# part_2.net
KiCad netlist of a schematic drawn in EAGLE
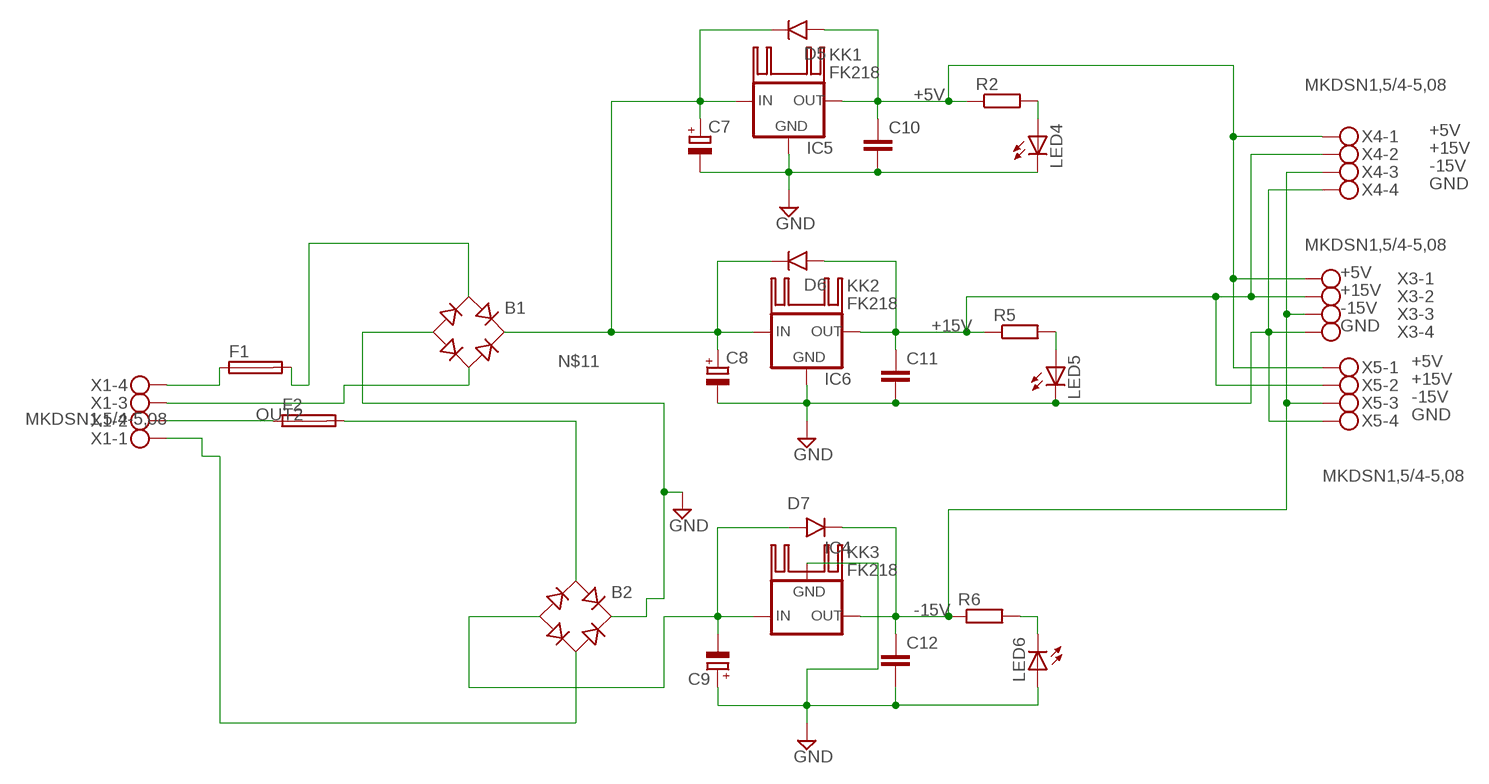
[diagram p0: schematic, sheet 1]

(export (version "E")
  (design (tool "Eeschema 10.0.6"))
  (components
    (comp (ref "B1")
      (value "RB1A")
      (footprint "eagle-import:RB1A")
      (libsource (lib "eagle-import") (part "RB1A"))
    )
    (comp (ref "B2")
      (value "RB1A")
      (footprint "eagle-import:RB1A")
      (libsource (lib "eagle-import") (part "RB1A"))
    )
    (comp (ref "C7")
      (value "CPOL-EUE7.5-18")
      (footprint "eagle-import:E7,5-18")
      (libsource (lib "eagle-import") (part "CPOL-EUE7.5-18"))
    )
    (comp (ref "C8")
      (value "CPOL-EUE7.5-18")
      (footprint "eagle-import:E7,5-18")
      (libsource (lib "eagle-import") (part "CPOL-EUE7.5-18"))
    )
    (comp (ref "C9")
      (value "CPOL-EUE7.5-18")
      (footprint "eagle-import:E7,5-18")
      (libsource (lib "eagle-import") (part "CPOL-EUE7.5-18"))
    )
    (comp (ref "C10")
      (value "C-EU050-025X075")
      (footprint "eagle-import:C050-025X075")
      (libsource (lib "eagle-import") (part "C-EU050-025X075"))
    )
    (comp (ref "C11")
      (value "C-EU050-025X075")
      (footprint "eagle-import:C050-025X075")
      (libsource (lib "eagle-import") (part "C-EU050-025X075"))
    )
    (comp (ref "C12")
      (value "C-EU050-025X075")
      (footprint "eagle-import:C050-025X075")
      (libsource (lib "eagle-import") (part "C-EU050-025X075"))
    )
    (comp (ref "D5")
      (value "1N4001")
      (footprint "eagle-import:DO41-10")
      (libsource (lib "eagle-import") (part "1N4001"))
    )
    (comp (ref "D6")
      (value "1N4001")
      (footprint "eagle-import:DO41-10")
      (libsource (lib "eagle-import") (part "1N4001"))
    )
    (comp (ref "D7")
      (value "1N4001")
      (footprint "eagle-import:DO41-10")
      (libsource (lib "eagle-import") (part "1N4001"))
    )
    (comp (ref "F1")
      (value "SH22,5A")
      (footprint "eagle-import:SH22,5A")
      (fields (field (name "MPN") "0031.7701.11"))
      (libsource (lib "eagle-import") (part "SH22,5A"))
    )
    (comp (ref "F2")
      (value "SH22,5A")
      (footprint "eagle-import:SH22,5A")
      (fields (field (name "MPN") "0031.7701.11"))
      (libsource (lib "eagle-import") (part "SH22,5A"))
    )
    (comp (ref "IC4")
      (value "79XXS")
      (footprint "eagle-import:79XXS")
      (libsource (lib "eagle-import") (part "79XXS"))
    )
    (comp (ref "IC5")
      (value "78XXS")
      (footprint "eagle-import:78XXS")
      (libsource (lib "eagle-import") (part "78XXS"))
    )
    (comp (ref "IC6")
      (value "78XXS")
      (footprint "eagle-import:78XXS")
      (libsource (lib "eagle-import") (part "78XXS"))
    )
    (comp (ref "KK1")
      (value "FK218")
      (footprint "eagle-import:FK218")
      (libsource (lib "eagle-import") (part "FK218"))
    )
    (comp (ref "KK2")
      (value "FK218")
      (footprint "eagle-import:FK218")
      (libsource (lib "eagle-import") (part "FK218"))
    )
    (comp (ref "KK3")
      (value "FK218")
      (footprint "eagle-import:FK218")
      (libsource (lib "eagle-import") (part "FK218"))
    )
    (comp (ref "LED4")
      (value "LED5MM")
      (footprint "eagle-import:LED5MM")
      (libsource (lib "eagle-import") (part "LED5MM"))
    )
    (comp (ref "LED5")
      (value "LED5MM")
      (footprint "eagle-import:LED5MM")
      (libsource (lib "eagle-import") (part "LED5MM"))
    )
    (comp (ref "LED6")
      (value "LED5MM")
      (footprint "eagle-import:LED5MM")
      (libsource (lib "eagle-import") (part "LED5MM"))
    )
    (comp (ref "R2")
      (value "R-EU_0207/15")
      (footprint "eagle-import:0207_15")
      (libsource (lib "eagle-import") (part "R-EU_0207/15"))
    )
    (comp (ref "R5")
      (value "R-EU_0207/15")
      (footprint "eagle-import:0207_15")
      (libsource (lib "eagle-import") (part "R-EU_0207/15"))
    )
    (comp (ref "R6")
      (value "R-EU_0207/15")
      (footprint "eagle-import:0207_15")
      (libsource (lib "eagle-import") (part "R-EU_0207/15"))
    )
    (comp (ref "X1")
      (value "MKDSN1,5/4-5,08")
      (footprint "eagle-import:MKDSN1,5_4-5,08")
      (libsource (lib "eagle-import") (part "MKDSN1,5/4-5,08"))
    )
    (comp (ref "X3")
      (value "MKDSN1,5/4-5,08")
      (footprint "eagle-import:MKDSN1,5_4-5,08")
      (libsource (lib "eagle-import") (part "MKDSN1,5/4-5,08"))
    )
    (comp (ref "X4")
      (value "MKDSN1,5/4-5,08")
      (footprint "eagle-import:MKDSN1,5_4-5,08")
      (libsource (lib "eagle-import") (part "MKDSN1,5/4-5,08"))
    )
    (comp (ref "X5")
      (value "MKDSN1,5/4-5,08")
      (footprint "eagle-import:MKDSN1,5_4-5,08")
      (libsource (lib "eagle-import") (part "MKDSN1,5/4-5,08"))
    )
  )
  (nets
    (net (code "1") (name "/+5V") (class "Default")
      (node (ref "C10") (pin "1") (pinfunction "1_1") (pintype "passive"))
      (node (ref "D5") (pin "A") (pinfunction "ANODE_A") (pintype "passive"))
      (node (ref "IC5") (pin "OUT") (pinfunction "OUT_OUT") (pintype "passive"))
      (node (ref "R2") (pin "1") (pinfunction "1_1") (pintype "passive"))
      (node (ref "X3") (pin "1") (pinfunction "KL_1") (pintype "passive"))
      (node (ref "X4") (pin "1") (pinfunction "KL_1") (pintype "passive"))
      (node (ref "X5") (pin "1") (pinfunction "KL_1") (pintype "passive"))
    )
    (net (code "2") (name "/+15V") (class "Default")
      (node (ref "C11") (pin "1") (pinfunction "1_1") (pintype "passive"))
      (node (ref "D6") (pin "A") (pinfunction "ANODE_A") (pintype "passive"))
      (node (ref "IC6") (pin "OUT") (pinfunction "OUT_OUT") (pintype "passive"))
      (node (ref "R5") (pin "1") (pinfunction "1_1") (pintype "passive"))
      (node (ref "X3") (pin "2") (pinfunction "KL_2") (pintype "passive"))
      (node (ref "X4") (pin "2") (pinfunction "KL_2") (pintype "passive"))
      (node (ref "X5") (pin "2") (pinfunction "KL_2") (pintype "passive"))
    )
    (net (code "3") (name "/-15V") (class "Default")
      (node (ref "C12") (pin "1") (pinfunction "1_1") (pintype "passive"))
      (node (ref "D7") (pin "C") (pinfunction "CATHODE_C") (pintype "passive"))
      (node (ref "IC4") (pin "OUT") (pinfunction "OUT_OUT") (pintype "passive"))
      (node (ref "R6") (pin "1") (pinfunction "1_1") (pintype "passive"))
      (node (ref "X3") (pin "3") (pinfunction "KL_3") (pintype "passive"))
      (node (ref "X4") (pin "3") (pinfunction "KL_3") (pintype "passive"))
      (node (ref "X5") (pin "3") (pinfunction "KL_3") (pintype "passive"))
    )
    (net (code "4") (name "/N$11") (class "Default")
      (node (ref "B1") (pin "+") (pinfunction "+_+") (pintype "passive"))
      (node (ref "C7") (pin "+") (pinfunction "+_+") (pintype "passive"))
      (node (ref "C8") (pin "+") (pinfunction "+_+") (pintype "passive"))
      (node (ref "D5") (pin "C") (pinfunction "CATHODE_C") (pintype "passive"))
      (node (ref "D6") (pin "C") (pinfunction "CATHODE_C") (pintype "passive"))
      (node (ref "IC5") (pin "IN") (pinfunction "IN_IN") (pintype "input"))
      (node (ref "IC6") (pin "IN") (pinfunction "IN_IN") (pintype "input"))
    )
    (net (code "5") (name "/OUT2") (class "Default")
      (node (ref "B1") (pin "AC2") (pinfunction "AC2_AC2") (pintype "passive"))
      (node (ref "X1") (pin "3") (pinfunction "KL_3") (pintype "passive"))
    )
    (net (code "6") (name "GND") (class "Default")
      (node (ref "B1") (pin "-") (pinfunction "-_-") (pintype "passive"))
      (node (ref "B2") (pin "+") (pinfunction "+_+") (pintype "passive"))
      (node (ref "C10") (pin "2") (pinfunction "2_2") (pintype "passive"))
      (node (ref "C11") (pin "2") (pinfunction "2_2") (pintype "passive"))
      (node (ref "C12") (pin "2") (pinfunction "2_2") (pintype "passive"))
      (node (ref "C7") (pin "-") (pinfunction "-_-") (pintype "passive"))
      (node (ref "C8") (pin "-") (pinfunction "-_-") (pintype "passive"))
      (node (ref "C9") (pin "+") (pinfunction "+_+") (pintype "passive"))
      (node (ref "IC4") (pin "GND") (pinfunction "GND_GND") (pintype "input"))
      (node (ref "IC5") (pin "GND") (pinfunction "GND_GND") (pintype "input"))
      (node (ref "IC6") (pin "GND") (pinfunction "GND_GND") (pintype "input"))
      (node (ref "LED4") (pin "K") (pinfunction "C_K") (pintype "passive"))
      (node (ref "LED5") (pin "K") (pinfunction "C_K") (pintype "passive"))
      (node (ref "LED6") (pin "A") (pinfunction "A_A") (pintype "passive"))
      (node (ref "X3") (pin "4") (pinfunction "KL_4") (pintype "passive"))
      (node (ref "X4") (pin "4") (pinfunction "KL_4") (pintype "passive"))
      (node (ref "X5") (pin "4") (pinfunction "KL_4") (pintype "passive"))
    )
    (net (code "7") (name "Net-(B1-PadAC1)") (class "Default")
      (node (ref "B1") (pin "AC1") (pinfunction "AC1_AC1") (pintype "passive"))
      (node (ref "F1") (pin "2") (pinfunction "2_2") (pintype "passive"))
    )
    (net (code "8") (name "Net-(B2-PadAC1)") (class "Default")
      (node (ref "B2") (pin "AC1") (pinfunction "AC1_AC1") (pintype "passive"))
      (node (ref "F2") (pin "2") (pinfunction "2_2") (pintype "passive"))
    )
    (net (code "9") (name "Net-(D7-ANODE)") (class "Default")
      (node (ref "B2") (pin "-") (pinfunction "-_-") (pintype "passive"))
      (node (ref "C9") (pin "-") (pinfunction "-_-") (pintype "passive"))
      (node (ref "D7") (pin "A") (pinfunction "ANODE_A") (pintype "passive"))
      (node (ref "IC4") (pin "IN") (pinfunction "IN_IN") (pintype "input"))
    )
    (net (code "10") (name "Net-(LED4-PadA)") (class "Default")
      (node (ref "LED4") (pin "A") (pinfunction "A_A") (pintype "passive"))
      (node (ref "R2") (pin "2") (pinfunction "2_2") (pintype "passive"))
    )
    (net (code "11") (name "Net-(LED5-PadA)") (class "Default")
      (node (ref "LED5") (pin "A") (pinfunction "A_A") (pintype "passive"))
      (node (ref "R5") (pin "2") (pinfunction "2_2") (pintype "passive"))
    )
    (net (code "12") (name "Net-(LED6-C)") (class "Default")
      (node (ref "LED6") (pin "K") (pinfunction "C_K") (pintype "passive"))
      (node (ref "R6") (pin "2") (pinfunction "2_2") (pintype "passive"))
    )
    (net (code "13") (name "Net-(X1A-KL)") (class "Default")
      (node (ref "B2") (pin "AC2") (pinfunction "AC2_AC2") (pintype "passive"))
      (node (ref "X1") (pin "1") (pinfunction "KL_1") (pintype "passive"))
    )
    (net (code "14") (name "Net-(X1B-KL)") (class "Default")
      (node (ref "F2") (pin "1") (pinfunction "1_1") (pintype "passive"))
      (node (ref "X1") (pin "2") (pinfunction "KL_2") (pintype "passive"))
    )
    (net (code "15") (name "Net-(X1D-KL)") (class "Default")
      (node (ref "F1") (pin "1") (pinfunction "1_1") (pintype "passive"))
      (node (ref "X1") (pin "4") (pinfunction "KL_4") (pintype "passive"))
    )
    (net (code "16") (name "unconnected-(KK1-K-PadA2,2)") (class "Default")
      (node (ref "KK1") (pin "A2,2") (pinfunction "K_A2,2") (pintype "passive"))
    )
    (net (code "17") (name "unconnected-(KK1-K-PadB2,2)") (class "Default")
      (node (ref "KK1") (pin "B2,2") (pinfunction "K_B2,2") (pintype "passive"))
    )
    (net (code "18") (name "unconnected-(KK2-K-PadA2,2)") (class "Default")
      (node (ref "KK2") (pin "A2,2") (pinfunction "K_A2,2") (pintype "passive"))
    )
    (net (code "19") (name "unconnected-(KK2-K-PadB2,2)") (class "Default")
      (node (ref "KK2") (pin "B2,2") (pinfunction "K_B2,2") (pintype "passive"))
    )
    (net (code "20") (name "unconnected-(KK3-K-PadA2,2)") (class "Default")
      (node (ref "KK3") (pin "A2,2") (pinfunction "K_A2,2") (pintype "passive"))
    )
    (net (code "21") (name "unconnected-(KK3-K-PadB2,2)") (class "Default")
      (node (ref "KK3") (pin "B2,2") (pinfunction "K_B2,2") (pintype "passive"))
    )
  )
)
